# IRTHERMV1_1.net
KiCad netlist of a schematic drawn in EAGLE
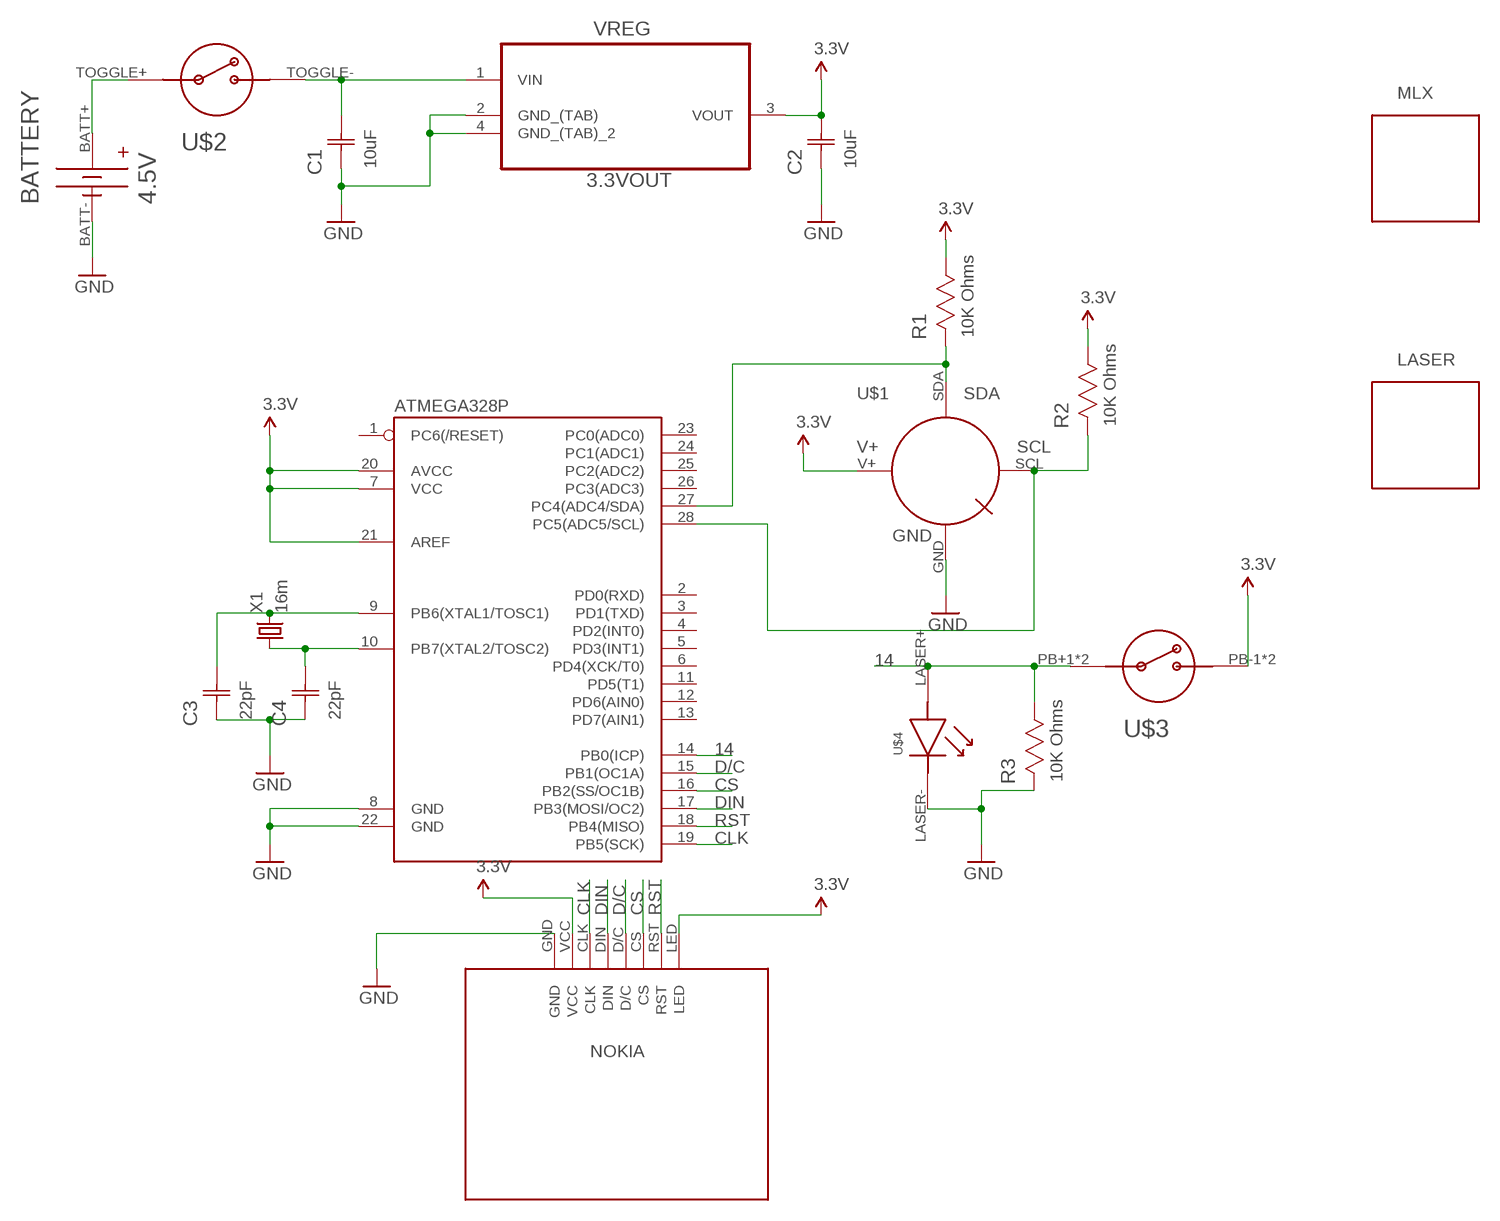
[diagram p0: schematic, sheet 1]

(export (version "E")
  (design (tool "Eeschema 10.0.6"))
  (components
    (comp (ref "ATMEGA328P")
      (value "ATMEGA328P_PDIP")
      (footprint "eagle-import:DIL28-3")
      (libsource (lib "eagle-import") (part "ATMEGA328P_PDIP"))
    )
    (comp (ref "BATTERY")
      (value "4.5V")
      (footprint "eagle-import:KEYSTONE2479")
      (libsource (lib "eagle-import") (part "KEYSTONE2479"))
    )
    (comp (ref "C1")
      (value "10uF")
      (footprint "eagle-import:CAPC3216X180N")
      (fields (field (name "MPN") "C1206C106K4RACTU") (field (name "TOLERANCE") "±10%"))
      (libsource (lib "eagle-import") (part "C1206C106K4RACTU"))
    )
    (comp (ref "C2")
      (value "10uF")
      (footprint "eagle-import:CAPC3216X180N")
      (fields (field (name "MPN") "C1206C106K4RACTU") (field (name "TOLERANCE") "±10%"))
      (libsource (lib "eagle-import") (part "C1206C106K4RACTU"))
    )
    (comp (ref "C3")
      (value "22pF")
      (footprint "eagle-import:CAPC3216X88N")
      (fields (field (name "MPN") "C1206C220J5GACTU") (field (name "TOLERANCE") "±5%"))
      (libsource (lib "eagle-import") (part "C1206C220J5GACTU"))
    )
    (comp (ref "C4")
      (value "22pF")
      (footprint "eagle-import:CAPC3216X88N")
      (fields (field (name "MPN") "C1206C220J5GACTU") (field (name "TOLERANCE") "±5%"))
      (libsource (lib "eagle-import") (part "C1206C220J5GACTU"))
    )
    (comp (ref "LASER")
      (value "KEYSTONECLIP")
      (footprint "eagle-import:KEYSTONE50")
      (libsource (lib "eagle-import") (part "KEYSTONECLIP"))
    )
    (comp (ref "MLX")
      (value "KEYSTONECLIP")
      (footprint "eagle-import:KEYSTONE50")
      (libsource (lib "eagle-import") (part "KEYSTONECLIP"))
    )
    (comp (ref "R1")
      (value "10K Ohms")
      (footprint "eagle-import:RESC3216X71N")
      (fields (field (name "MPN") "CRCW120610K0JNEA") (field (name "TOLERANCE") "±5%"))
      (libsource (lib "eagle-import") (part "CRCW120610K0JNEA"))
    )
    (comp (ref "R2")
      (value "10K Ohms")
      (footprint "eagle-import:RESC3216X71N")
      (fields (field (name "MPN") "CRCW120610K0JNEA") (field (name "TOLERANCE") "±5%"))
      (libsource (lib "eagle-import") (part "CRCW120610K0JNEA"))
    )
    (comp (ref "R3")
      (value "10K Ohms")
      (footprint "eagle-import:RESC3216X71N")
      (fields (field (name "MPN") "CRCW120610K0JNEA") (field (name "TOLERANCE") "±5%"))
      (libsource (lib "eagle-import") (part "CRCW120610K0JNEA"))
    )
    (comp (ref "U$1")
      (value "MLX90614")
      (footprint "eagle-import:MLX90614")
      (libsource (lib "eagle-import") (part "MLX90614"))
    )
    (comp (ref "U$2")
      (value "1683ON-OFFTOGGLE")
      (footprint "eagle-import:1683ON-OFFTOGGLE")
      (libsource (lib "eagle-import") (part "1683ON-OFFTOGGLE"))
    )
    (comp (ref "U$3")
      (value "1009PUSHBUTTON")
      (footprint "eagle-import:1009PUSHBUTTON")
      (libsource (lib "eagle-import") (part "1009PUSHBUTTON"))
    )
    (comp (ref "U$4")
      (value "LASER")
      (footprint "eagle-import:LASER")
      (libsource (lib "eagle-import") (part "LASER"))
    )
    (comp (ref "U$5")
      (value "NOKIA")
      (footprint "eagle-import:NOKIA")
      (libsource (lib "eagle-import") (part "NOKIA"))
    )
    (comp (ref "VREG")
      (value "3.3VOUT")
      (footprint "eagle-import:SOT230P700X180-4N")
      (fields (field (name "MPN") "MCP1824ST-3302E/DB"))
      (libsource (lib "eagle-import") (part "MCP1824ST-3302E/DB"))
    )
    (comp (ref "X1")
      (value "16m")
      (footprint "eagle-import:HC49US")
      (libsource (lib "eagle-import") (part "CRYSTALHC49US"))
    )
  )
  (nets
    (net (code "1") (name "/14") (class "Default")
      (node (ref "ATMEGA328P") (pin "14") (pinfunction "PB0(ICP)_14") (pintype "bidirectional"))
      (node (ref "R3") (pin "1") (pinfunction "1_1") (pintype "passive"))
      (node (ref "U$3") (pin "PB+1") (pinfunction "ONOFF+_PB+1") (pintype "bidirectional"))
      (node (ref "U$3") (pin "PB+2") (pinfunction "ONOFF+_PB+2") (pintype "bidirectional"))
      (node (ref "U$4") (pin "LASER+") (pinfunction "LASER+_LASER+") (pintype "bidirectional"))
    )
    (net (code "2") (name "/CLK") (class "Default")
      (node (ref "ATMEGA328P") (pin "19") (pinfunction "PB5(SCK)_19") (pintype "bidirectional"))
      (node (ref "U$5") (pin "CLK") (pinfunction "CLK_CLK") (pintype "bidirectional"))
    )
    (net (code "3") (name "/CS") (class "Default")
      (node (ref "ATMEGA328P") (pin "16") (pinfunction "PB2(SS/OC1B)_16") (pintype "bidirectional"))
      (node (ref "U$5") (pin "CS") (pinfunction "CS_CS") (pintype "bidirectional"))
    )
    (net (code "4") (name "/DIN") (class "Default")
      (node (ref "ATMEGA328P") (pin "17") (pinfunction "PB3(MOSI/OC2)_17") (pintype "bidirectional"))
      (node (ref "U$5") (pin "DIN") (pinfunction "DIN_DIN") (pintype "bidirectional"))
    )
    (net (code "5") (name "/D{slash}C") (class "Default")
      (node (ref "ATMEGA328P") (pin "15") (pinfunction "PB1(OC1A)_15") (pintype "bidirectional"))
      (node (ref "U$5") (pin "D/C") (pinfunction "D/C_D/C") (pintype "bidirectional"))
    )
    (net (code "6") (name "/RST") (class "Default")
      (node (ref "ATMEGA328P") (pin "18") (pinfunction "PB4(MISO)_18") (pintype "bidirectional"))
      (node (ref "U$5") (pin "RST") (pinfunction "RST_RST") (pintype "bidirectional"))
    )
    (net (code "7") (name "3.3V") (class "Default")
      (node (ref "ATMEGA328P") (pin "20") (pinfunction "AVCC_20") (pintype "bidirectional"))
      (node (ref "ATMEGA328P") (pin "21") (pinfunction "AREF_21") (pintype "bidirectional"))
      (node (ref "ATMEGA328P") (pin "7") (pinfunction "VCC_7") (pintype "bidirectional"))
      (node (ref "C2") (pin "2") (pinfunction "C2_2") (pintype "passive"))
      (node (ref "R1") (pin "1") (pinfunction "1_1") (pintype "passive"))
      (node (ref "R2") (pin "1") (pinfunction "1_1") (pintype "passive"))
      (node (ref "U$1") (pin "V+") (pinfunction "MLXV+_V+") (pintype "bidirectional"))
      (node (ref "U$3") (pin "PB-1") (pinfunction "ONOFF-_PB-1") (pintype "bidirectional"))
      (node (ref "U$3") (pin "PB-2") (pinfunction "ONOFF-_PB-2") (pintype "bidirectional"))
      (node (ref "U$5") (pin "LED") (pinfunction "LED_LED") (pintype "bidirectional"))
      (node (ref "U$5") (pin "VCC") (pinfunction "VCC_VCC") (pintype "bidirectional"))
      (node (ref "VREG") (pin "3") (pinfunction "VOUT_3") (pintype "output"))
    )
    (net (code "8") (name "GND") (class "Default")
      (node (ref "ATMEGA328P") (pin "22") (pinfunction "GND_22") (pintype "bidirectional"))
      (node (ref "ATMEGA328P") (pin "8") (pinfunction "GND_8") (pintype "bidirectional"))
      (node (ref "BATTERY") (pin "BATT-") (pinfunction "BATT-_BATT-") (pintype "bidirectional"))
      (node (ref "C1") (pin "1") (pinfunction "C1_1") (pintype "passive"))
      (node (ref "C2") (pin "1") (pinfunction "C1_1") (pintype "passive"))
      (node (ref "C3") (pin "1") (pinfunction "C1_1") (pintype "passive"))
      (node (ref "C4") (pin "1") (pinfunction "C1_1") (pintype "passive"))
      (node (ref "R3") (pin "2") (pinfunction "2_2") (pintype "passive"))
      (node (ref "U$1") (pin "GND") (pinfunction "MLXGND_GND") (pintype "bidirectional"))
      (node (ref "U$4") (pin "LASER-") (pinfunction "LASERGND_LASER-") (pintype "bidirectional"))
      (node (ref "U$5") (pin "GND") (pinfunction "GND_GND") (pintype "bidirectional"))
      (node (ref "VREG") (pin "2") (pinfunction "GND_(TAB)_2") (pintype "passive"))
      (node (ref "VREG") (pin "4") (pinfunction "GND_(TAB)_2_4") (pintype "passive"))
    )
    (net (code "9") (name "Net-(ATMEGA328P-PB6(XTAL1{slash}TOSC1))") (class "Default")
      (node (ref "ATMEGA328P") (pin "9") (pinfunction "PB6(XTAL1/TOSC1)_9") (pintype "bidirectional"))
      (node (ref "C3") (pin "2") (pinfunction "C2_2") (pintype "passive"))
      (node (ref "X1") (pin "2") (pinfunction "2_2") (pintype "passive"))
    )
    (net (code "10") (name "Net-(ATMEGA328P-PB7(XTAL2{slash}TOSC2))") (class "Default")
      (node (ref "ATMEGA328P") (pin "10") (pinfunction "PB7(XTAL2/TOSC2)_10") (pintype "bidirectional"))
      (node (ref "C4") (pin "2") (pinfunction "C2_2") (pintype "passive"))
      (node (ref "X1") (pin "1") (pinfunction "1_1") (pintype "passive"))
    )
    (net (code "11") (name "Net-(ATMEGA328P-PC4(ADC4{slash}SDA))") (class "Default")
      (node (ref "ATMEGA328P") (pin "27") (pinfunction "PC4(ADC4/SDA)_27") (pintype "bidirectional"))
      (node (ref "R1") (pin "2") (pinfunction "2_2") (pintype "passive"))
      (node (ref "U$1") (pin "SDA") (pinfunction "MLXSDA_SDA") (pintype "bidirectional"))
    )
    (net (code "12") (name "Net-(ATMEGA328P-PC5(ADC5{slash}SCL))") (class "Default")
      (node (ref "ATMEGA328P") (pin "28") (pinfunction "PC5(ADC5/SCL)_28") (pintype "bidirectional"))
      (node (ref "R2") (pin "2") (pinfunction "2_2") (pintype "passive"))
      (node (ref "U$1") (pin "SCL") (pinfunction "MLXSCL_SCL") (pintype "bidirectional"))
    )
    (net (code "13") (name "Net-(C1-C2)") (class "Default")
      (node (ref "C1") (pin "2") (pinfunction "C2_2") (pintype "passive"))
      (node (ref "U$2") (pin "TOGGLE-") (pinfunction "ONOFF-_TOGGLE-") (pintype "bidirectional"))
      (node (ref "VREG") (pin "1") (pinfunction "VIN_1") (pintype "input"))
    )
    (net (code "14") (name "Net-(U$2-ONOFF+)") (class "Default")
      (node (ref "BATTERY") (pin "BATT+") (pinfunction "BATT+_BATT+") (pintype "bidirectional"))
      (node (ref "U$2") (pin "TOGGLE+") (pinfunction "ONOFF+_TOGGLE+") (pintype "bidirectional"))
    )
    (net (code "15") (name "unconnected-(ATMEGA328P-PC0(ADC0)-Pad23)") (class "Default")
      (node (ref "ATMEGA328P") (pin "23") (pinfunction "PC0(ADC0)_23") (pintype "bidirectional"))
    )
    (net (code "16") (name "unconnected-(ATMEGA328P-PC1(ADC1)-Pad24)") (class "Default")
      (node (ref "ATMEGA328P") (pin "24") (pinfunction "PC1(ADC1)_24") (pintype "bidirectional"))
    )
    (net (code "17") (name "unconnected-(ATMEGA328P-PC2(ADC2)-Pad25)") (class "Default")
      (node (ref "ATMEGA328P") (pin "25") (pinfunction "PC2(ADC2)_25") (pintype "bidirectional"))
    )
    (net (code "18") (name "unconnected-(ATMEGA328P-PC3(ADC3)-Pad26)") (class "Default")
      (node (ref "ATMEGA328P") (pin "26") (pinfunction "PC3(ADC3)_26") (pintype "bidirectional"))
    )
    (net (code "19") (name "unconnected-(ATMEGA328P-PC6({slash}RESET)-Pad1)") (class "Default")
      (node (ref "ATMEGA328P") (pin "1") (pinfunction "PC6(/RESET)_1") (pintype "bidirectional"))
    )
    (net (code "20") (name "unconnected-(ATMEGA328P-PD0(RXD)-Pad2)") (class "Default")
      (node (ref "ATMEGA328P") (pin "2") (pinfunction "PD0(RXD)_2") (pintype "bidirectional"))
    )
    (net (code "21") (name "unconnected-(ATMEGA328P-PD1(TXD)-Pad3)") (class "Default")
      (node (ref "ATMEGA328P") (pin "3") (pinfunction "PD1(TXD)_3") (pintype "bidirectional"))
    )
    (net (code "22") (name "unconnected-(ATMEGA328P-PD2(INT0)-Pad4)") (class "Default")
      (node (ref "ATMEGA328P") (pin "4") (pinfunction "PD2(INT0)_4") (pintype "bidirectional"))
    )
    (net (code "23") (name "unconnected-(ATMEGA328P-PD3(INT1)-Pad5)") (class "Default")
      (node (ref "ATMEGA328P") (pin "5") (pinfunction "PD3(INT1)_5") (pintype "bidirectional"))
    )
    (net (code "24") (name "unconnected-(ATMEGA328P-PD4(XCK{slash}T0)-Pad6)") (class "Default")
      (node (ref "ATMEGA328P") (pin "6") (pinfunction "PD4(XCK/T0)_6") (pintype "bidirectional"))
    )
    (net (code "25") (name "unconnected-(ATMEGA328P-PD5(T1)-Pad11)") (class "Default")
      (node (ref "ATMEGA328P") (pin "11") (pinfunction "PD5(T1)_11") (pintype "bidirectional"))
    )
    (net (code "26") (name "unconnected-(ATMEGA328P-PD6(AIN0)-Pad12)") (class "Default")
      (node (ref "ATMEGA328P") (pin "12") (pinfunction "PD6(AIN0)_12") (pintype "bidirectional"))
    )
    (net (code "27") (name "unconnected-(ATMEGA328P-PD7(AIN1)-Pad13)") (class "Default")
      (node (ref "ATMEGA328P") (pin "13") (pinfunction "PD7(AIN1)_13") (pintype "bidirectional"))
    )
  )
)
